# On_Off_switch.net
KiCad netlist of a schematic drawn in Altium Designer
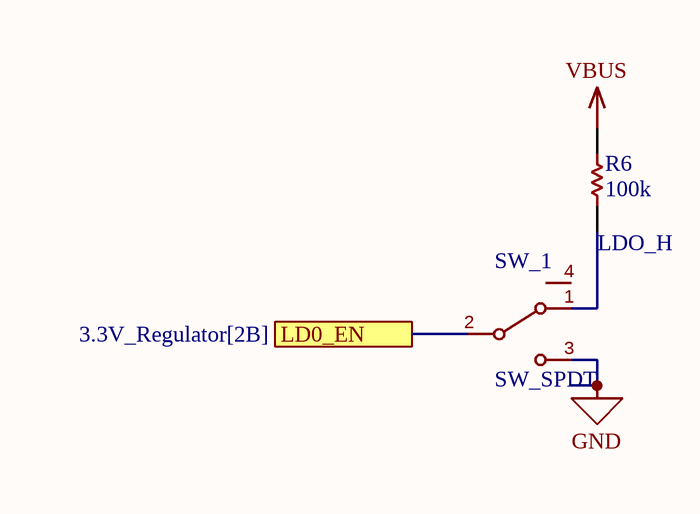
[diagram p0: On_Off_switch.SchDoc]

(export (version "E")
  (design (tool "Eeschema 10.0.6"))
  (components
    (comp (ref "R6")
      (value "100k")
      (footprint "RESC2013X70X40NL20T20")
      (description "Chip Resistor, 1 KOhm, +/- 1%, 125 mW, -55 to 155 degC, 0805 (2012 Metric), RoHS, Tape and Reel")
      (fields (field (name "TOLERANCE") "1%") (field (name "MANUFACTURER") "Yageo"))
      (libsource (lib "Thermal_Camera") (part "CMP-2100-03671-1"))
    )
    (comp (ref "SW_1")
      (value "SW_SPDT")
      (footprint "SW_MPB06-1C00-R-SMT-TR")
      (libsource (lib "Thermal_Camera") (part "SW_SPDT"))
    )
  )
  (nets
    (net (code "1") (name "/LD0_EN") (class "Default")
      (node (ref "SW_1") (pin "2") (pinfunction "B_2") (pintype "passive"))
    )
    (net (code "2") (name "GND") (class "Default")
      (node (ref "SW_1") (pin "3") (pinfunction "C_3") (pintype "passive"))
    )
    (net (code "3") (name "Net-(SW_1-A)") (class "Default")
      (node (ref "R6") (pin "1") (pinfunction "1_1") (pintype "passive"))
      (node (ref "SW_1") (pin "1") (pinfunction "A_1") (pintype "passive"))
    )
    (net (code "4") (name "VBUS") (class "Default")
      (node (ref "R6") (pin "2") (pinfunction "2_2") (pintype "passive"))
    )
    (net (code "5") (name "unconnected-(SW_1-Pad4)") (class "Default")
      (node (ref "SW_1") (pin "4") (pinfunction "4_4") (pintype "passive"))
    )
  )
)
